# nano_bt_mx.net
KiCad netlist of a schematic drawn in EAGLE
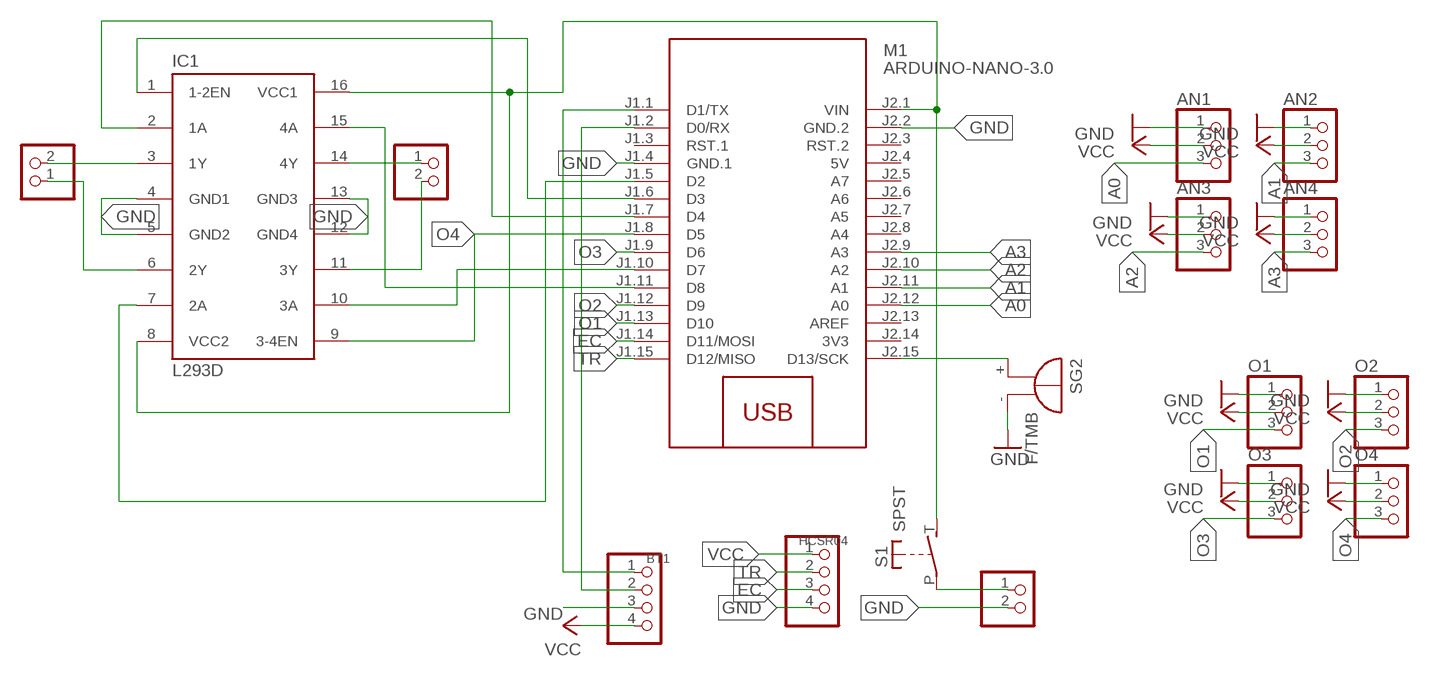
[diagram p0: schematic, sheet 1]

(export (version "E")
  (design (tool "Eeschema 10.0.6"))
  (components
    (comp (ref "AN1")
      (value "PINHD-1X3")
      (footprint "eagle-import:1X03")
      (libsource (lib "eagle-import") (part "PINHD-1X3"))
    )
    (comp (ref "AN2")
      (value "PINHD-1X3")
      (footprint "eagle-import:1X03")
      (libsource (lib "eagle-import") (part "PINHD-1X3"))
    )
    (comp (ref "AN3")
      (value "PINHD-1X3")
      (footprint "eagle-import:1X03")
      (libsource (lib "eagle-import") (part "PINHD-1X3"))
    )
    (comp (ref "AN4")
      (value "PINHD-1X3")
      (footprint "eagle-import:1X03")
      (libsource (lib "eagle-import") (part "PINHD-1X3"))
    )
    (comp (ref "BT1")
      (value "PINHD-1X4")
      (footprint "eagle-import:1X04")
      (libsource (lib "eagle-import") (part "PINHD-1X4"))
    )
    (comp (ref "DCV")
      (value "PINHD-1X2")
      (footprint "eagle-import:1X02")
      (libsource (lib "eagle-import") (part "PINHD-1X2"))
    )
    (comp (ref "HCSR04")
      (value "PINHD-1X4")
      (footprint "eagle-import:1X04")
      (libsource (lib "eagle-import") (part "PINHD-1X4"))
    )
    (comp (ref "IC1")
      (value "L293D")
      (footprint "eagle-import:DIL16")
      (libsource (lib "eagle-import") (part "L293D"))
    )
    (comp (ref "M1")
      (value "ARDUINO-NANO-3.0")
      (footprint "eagle-import:ARDUINO-NANO-3.0")
      (libsource (lib "eagle-import") (part "ARDUINO-NANO-3.0"))
    )
    (comp (ref "MT1")
      (value "PINHD-1X2")
      (footprint "eagle-import:1X02")
      (libsource (lib "eagle-import") (part "PINHD-1X2"))
    )
    (comp (ref "MT2")
      (value "PINHD-1X2")
      (footprint "eagle-import:1X02")
      (libsource (lib "eagle-import") (part "PINHD-1X2"))
    )
    (comp (ref "O1")
      (value "PINHD-1X3")
      (footprint "eagle-import:1X03")
      (libsource (lib "eagle-import") (part "PINHD-1X3"))
    )
    (comp (ref "O2")
      (value "PINHD-1X3")
      (footprint "eagle-import:1X03")
      (libsource (lib "eagle-import") (part "PINHD-1X3"))
    )
    (comp (ref "O3")
      (value "PINHD-1X3")
      (footprint "eagle-import:1X03")
      (libsource (lib "eagle-import") (part "PINHD-1X3"))
    )
    (comp (ref "O4")
      (value "PINHD-1X3")
      (footprint "eagle-import:1X03")
      (libsource (lib "eagle-import") (part "PINHD-1X3"))
    )
    (comp (ref "S1")
      (value "SPST")
      (footprint "eagle-import:JUDCOSPST")
      (libsource (lib "eagle-import") (part "SPST"))
    )
    (comp (ref "SG2")
      (value "F/TMB")
      (footprint "eagle-import:F_TMB")
      (libsource (lib "eagle-import") (part "F/TMB"))
    )
  )
  (nets
    (net (code "1") (name "/3V3") (class "Default")
      (node (ref "M1") (pin "J2.14") (pinfunction "3V3_J2.14") (pintype "power_in"))
    )
    (net (code "2") (name "/5V") (class "Default")
      (node (ref "M1") (pin "J2.4") (pinfunction "5V_J2.4") (pintype "power_in"))
    )
    (net (code "3") (name "A0") (class "Default")
      (node (ref "AN1") (pin "3") (pinfunction "3_3") (pintype "passive"))
      (node (ref "M1") (pin "J2.12") (pinfunction "A0_J2.12") (pintype "bidirectional"))
    )
    (net (code "4") (name "A1") (class "Default")
      (node (ref "AN2") (pin "3") (pinfunction "3_3") (pintype "passive"))
      (node (ref "M1") (pin "J2.11") (pinfunction "A1_J2.11") (pintype "bidirectional"))
    )
    (net (code "5") (name "A2") (class "Default")
      (node (ref "AN3") (pin "3") (pinfunction "3_3") (pintype "passive"))
      (node (ref "M1") (pin "J2.10") (pinfunction "A2_J2.10") (pintype "bidirectional"))
    )
    (net (code "6") (name "A3") (class "Default")
      (node (ref "AN4") (pin "3") (pinfunction "3_3") (pintype "passive"))
      (node (ref "M1") (pin "J2.9") (pinfunction "A3_J2.9") (pintype "bidirectional"))
    )
    (net (code "7") (name "EC") (class "Default")
      (node (ref "HCSR04") (pin "3") (pinfunction "3_3") (pintype "passive"))
      (node (ref "M1") (pin "J1.14") (pinfunction "D11/MOSI_J1.14") (pintype "bidirectional"))
    )
    (net (code "8") (name "GND") (class "Default")
      (node (ref "AN1") (pin "1") (pinfunction "1_1") (pintype "passive"))
      (node (ref "AN2") (pin "1") (pinfunction "1_1") (pintype "passive"))
      (node (ref "AN3") (pin "1") (pinfunction "1_1") (pintype "passive"))
      (node (ref "AN4") (pin "1") (pinfunction "1_1") (pintype "passive"))
      (node (ref "BT1") (pin "3") (pinfunction "3_3") (pintype "passive"))
      (node (ref "DCV") (pin "2") (pinfunction "2_2") (pintype "passive"))
      (node (ref "HCSR04") (pin "4") (pinfunction "4_4") (pintype "passive"))
      (node (ref "IC1") (pin "12") (pinfunction "GND4_12") (pintype "power_in"))
      (node (ref "IC1") (pin "13") (pinfunction "GND3_13") (pintype "power_in"))
      (node (ref "IC1") (pin "4") (pinfunction "GND1_4") (pintype "power_in"))
      (node (ref "IC1") (pin "5") (pinfunction "GND2_5") (pintype "power_in"))
      (node (ref "M1") (pin "J1.4") (pinfunction "GND.1_J1.4") (pintype "power_in"))
      (node (ref "M1") (pin "J2.2") (pinfunction "GND.2_J2.2") (pintype "power_in"))
      (node (ref "O1") (pin "1") (pinfunction "1_1") (pintype "passive"))
      (node (ref "O2") (pin "1") (pinfunction "1_1") (pintype "passive"))
      (node (ref "O3") (pin "1") (pinfunction "1_1") (pintype "passive"))
      (node (ref "O4") (pin "1") (pinfunction "1_1") (pintype "passive"))
      (node (ref "SG2") (pin "-") (pinfunction "-_-") (pintype "passive"))
    )
    (net (code "9") (name "Net-(DCV-Pad1)") (class "Default")
      (node (ref "DCV") (pin "1") (pinfunction "1_1") (pintype "passive"))
      (node (ref "S1") (pin "P") (pinfunction "P_P") (pintype "passive"))
    )
    (net (code "10") (name "Net-(IC1-1-2EN)") (class "Default")
      (node (ref "IC1") (pin "1") (pinfunction "1-2EN_1") (pintype "input"))
      (node (ref "M1") (pin "J1.6") (pinfunction "D3_J1.6") (pintype "bidirectional"))
    )
    (net (code "11") (name "Net-(IC1-1A)") (class "Default")
      (node (ref "IC1") (pin "2") (pinfunction "1A_2") (pintype "input"))
      (node (ref "M1") (pin "J1.7") (pinfunction "D4_J1.7") (pintype "bidirectional"))
    )
    (net (code "12") (name "Net-(IC1-1Y)") (class "Default")
      (node (ref "IC1") (pin "3") (pinfunction "1Y_3") (pintype "output"))
      (node (ref "MT1") (pin "2") (pinfunction "2_2") (pintype "passive"))
    )
    (net (code "13") (name "Net-(IC1-2A)") (class "Default")
      (node (ref "IC1") (pin "7") (pinfunction "2A_7") (pintype "input"))
      (node (ref "M1") (pin "J1.5") (pinfunction "D2_J1.5") (pintype "bidirectional"))
    )
    (net (code "14") (name "Net-(IC1-2Y)") (class "Default")
      (node (ref "IC1") (pin "6") (pinfunction "2Y_6") (pintype "output"))
      (node (ref "MT1") (pin "1") (pinfunction "1_1") (pintype "passive"))
    )
    (net (code "15") (name "Net-(IC1-3A)") (class "Default")
      (node (ref "IC1") (pin "10") (pinfunction "3A_10") (pintype "input"))
      (node (ref "M1") (pin "J1.10") (pinfunction "D7_J1.10") (pintype "bidirectional"))
    )
    (net (code "16") (name "Net-(IC1-3Y)") (class "Default")
      (node (ref "IC1") (pin "11") (pinfunction "3Y_11") (pintype "output"))
      (node (ref "MT2") (pin "2") (pinfunction "2_2") (pintype "passive"))
    )
    (net (code "17") (name "Net-(IC1-4A)") (class "Default")
      (node (ref "IC1") (pin "15") (pinfunction "4A_15") (pintype "input"))
      (node (ref "M1") (pin "J1.11") (pinfunction "D8_J1.11") (pintype "bidirectional"))
    )
    (net (code "18") (name "Net-(IC1-4Y)") (class "Default")
      (node (ref "IC1") (pin "14") (pinfunction "4Y_14") (pintype "output"))
      (node (ref "MT2") (pin "1") (pinfunction "1_1") (pintype "passive"))
    )
    (net (code "19") (name "Net-(IC1-VCC1)") (class "Default")
      (node (ref "IC1") (pin "16") (pinfunction "VCC1_16") (pintype "power_in"))
      (node (ref "IC1") (pin "8") (pinfunction "VCC2_8") (pintype "power_in"))
      (node (ref "M1") (pin "J2.1") (pinfunction "VIN_J2.1") (pintype "power_in"))
      (node (ref "S1") (pin "T") (pinfunction "S_T") (pintype "passive"))
    )
    (net (code "20") (name "Net-(M1-D0{slash}RX)") (class "Default")
      (node (ref "BT1") (pin "2") (pinfunction "2_2") (pintype "passive"))
      (node (ref "M1") (pin "J1.2") (pinfunction "D0/RX_J1.2") (pintype "bidirectional"))
    )
    (net (code "21") (name "Net-(M1-D1{slash}TX)") (class "Default")
      (node (ref "BT1") (pin "1") (pinfunction "1_1") (pintype "passive"))
      (node (ref "M1") (pin "J1.1") (pinfunction "D1/TX_J1.1") (pintype "bidirectional"))
    )
    (net (code "22") (name "Net-(M1-D13{slash}SCK)") (class "Default")
      (node (ref "M1") (pin "J2.15") (pinfunction "D13/SCK_J2.15") (pintype "bidirectional"))
      (node (ref "SG2") (pin "+") (pinfunction "+_+") (pintype "passive"))
    )
    (net (code "23") (name "O1") (class "Default")
      (node (ref "M1") (pin "J1.13") (pinfunction "D10_J1.13") (pintype "bidirectional"))
      (node (ref "O1") (pin "3") (pinfunction "3_3") (pintype "passive"))
    )
    (net (code "24") (name "O2") (class "Default")
      (node (ref "M1") (pin "J1.12") (pinfunction "D9_J1.12") (pintype "bidirectional"))
      (node (ref "O2") (pin "3") (pinfunction "3_3") (pintype "passive"))
    )
    (net (code "25") (name "O3") (class "Default")
      (node (ref "M1") (pin "J1.9") (pinfunction "D6_J1.9") (pintype "bidirectional"))
      (node (ref "O3") (pin "3") (pinfunction "3_3") (pintype "passive"))
    )
    (net (code "26") (name "O4") (class "Default")
      (node (ref "IC1") (pin "9") (pinfunction "3-4EN_9") (pintype "input"))
      (node (ref "M1") (pin "J1.8") (pinfunction "D5_J1.8") (pintype "bidirectional"))
      (node (ref "O4") (pin "3") (pinfunction "3_3") (pintype "passive"))
    )
    (net (code "27") (name "TR") (class "Default")
      (node (ref "HCSR04") (pin "2") (pinfunction "2_2") (pintype "passive"))
      (node (ref "M1") (pin "J1.15") (pinfunction "D12/MISO_J1.15") (pintype "bidirectional"))
    )
    (net (code "28") (name "VCC") (class "Default")
      (node (ref "AN1") (pin "2") (pinfunction "2_2") (pintype "passive"))
      (node (ref "AN2") (pin "2") (pinfunction "2_2") (pintype "passive"))
      (node (ref "AN3") (pin "2") (pinfunction "2_2") (pintype "passive"))
      (node (ref "AN4") (pin "2") (pinfunction "2_2") (pintype "passive"))
      (node (ref "BT1") (pin "4") (pinfunction "4_4") (pintype "passive"))
      (node (ref "HCSR04") (pin "1") (pinfunction "1_1") (pintype "passive"))
      (node (ref "O1") (pin "2") (pinfunction "2_2") (pintype "passive"))
      (node (ref "O2") (pin "2") (pinfunction "2_2") (pintype "passive"))
      (node (ref "O3") (pin "2") (pinfunction "2_2") (pintype "passive"))
      (node (ref "O4") (pin "2") (pinfunction "2_2") (pintype "passive"))
    )
    (net (code "29") (name "unconnected-(M1-A4-PadJ2.8)") (class "Default")
      (node (ref "M1") (pin "J2.8") (pinfunction "A4_J2.8") (pintype "bidirectional"))
    )
    (net (code "30") (name "unconnected-(M1-A5-PadJ2.7)") (class "Default")
      (node (ref "M1") (pin "J2.7") (pinfunction "A5_J2.7") (pintype "bidirectional"))
    )
    (net (code "31") (name "unconnected-(M1-A6-PadJ2.6)") (class "Default")
      (node (ref "M1") (pin "J2.6") (pinfunction "A6_J2.6") (pintype "bidirectional"))
    )
    (net (code "32") (name "unconnected-(M1-A7-PadJ2.5)") (class "Default")
      (node (ref "M1") (pin "J2.5") (pinfunction "A7_J2.5") (pintype "bidirectional"))
    )
    (net (code "33") (name "unconnected-(M1-AREF-PadJ2.13)") (class "Default")
      (node (ref "M1") (pin "J2.13") (pinfunction "AREF_J2.13") (pintype "bidirectional"))
    )
    (net (code "34") (name "unconnected-(M1-RST.1-PadJ1.3)") (class "Default")
      (node (ref "M1") (pin "J1.3") (pinfunction "RST.1_J1.3") (pintype "bidirectional"))
    )
    (net (code "35") (name "unconnected-(M1-RST.2-PadJ2.3)") (class "Default")
      (node (ref "M1") (pin "J2.3") (pinfunction "RST.2_J2.3") (pintype "bidirectional"))
    )
  )
)
